# sensor_v5_no_gnd.net
KiCad netlist of a schematic drawn in EAGLE
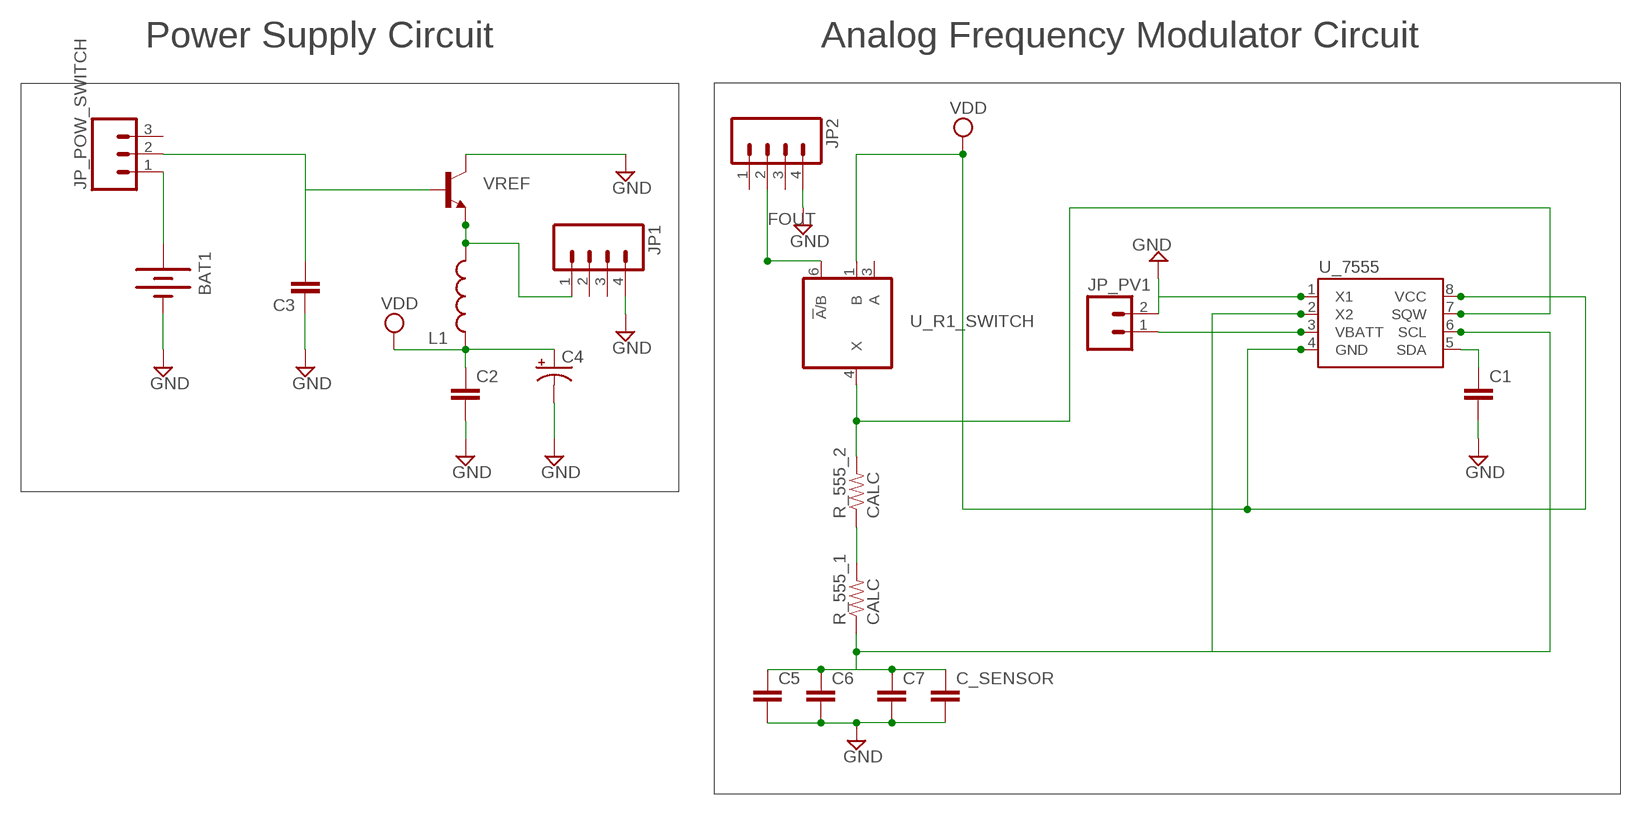
[diagram p0: schematic, sheet 1]

(export (version "E")
  (design (tool "Eeschema 10.0.6"))
  (components
    (comp (ref "BAT1")
      (value "BATTERY20PTH_LAB")
      (footprint "eagle-import:BATTCOM_20MM_PTH")
      (libsource (lib "eagle-import") (part "BATTERY20PTH_LAB"))
    )
    (comp (ref "C1")
      (value "CAP0603-CAP")
      (footprint "eagle-import:0603-CAP")
      (libsource (lib "eagle-import") (part "SparkFun-Capacitors_CAP0603-CAP"))
    )
    (comp (ref "C2")
      (value "CAP0603-CAP")
      (footprint "eagle-import:0603-CAP")
      (libsource (lib "eagle-import") (part "SparkFun-Capacitors_CAP0603-CAP"))
    )
    (comp (ref "C3")
      (value "CAP0603-CAP")
      (footprint "eagle-import:0603-CAP")
      (libsource (lib "eagle-import") (part "SparkFun-Capacitors_CAP0603-CAP"))
    )
    (comp (ref "C4")
      (value "CAP_POL1206")
      (footprint "eagle-import:EIA3216")
      (libsource (lib "eagle-import") (part "CAP_POL1206"))
    )
    (comp (ref "C5")
      (value "CAP0805")
      (footprint "eagle-import:0805")
      (libsource (lib "eagle-import") (part "CAP0805"))
    )
    (comp (ref "C6")
      (value "CAP0805")
      (footprint "eagle-import:0805")
      (libsource (lib "eagle-import") (part "CAP0805"))
    )
    (comp (ref "C7")
      (value "CAP0805")
      (footprint "eagle-import:0805")
      (libsource (lib "eagle-import") (part "CAP0805"))
    )
    (comp (ref "C_SENSOR")
      (value "CAP0805")
      (footprint "eagle-import:0805")
      (libsource (lib "eagle-import") (part "CAP0805"))
    )
    (comp (ref "JP1")
      (value "M04LOCK")
      (footprint "eagle-import:1X04_LOCK")
      (libsource (lib "eagle-import") (part "M04LOCK"))
    )
    (comp (ref "JP2")
      (value "M04LOCK")
      (footprint "eagle-import:1X04_LOCK")
      (libsource (lib "eagle-import") (part "M04LOCK"))
    )
    (comp (ref "JP_POW_SWITCH")
      (value "M03LOCK")
      (footprint "eagle-import:1X03_LOCK")
      (libsource (lib "eagle-import") (part "M03LOCK"))
    )
    (comp (ref "JP_PV1")
      (value "M02LOCK")
      (footprint "eagle-import:1X02_LOCK")
      (libsource (lib "eagle-import") (part "M02LOCK"))
    )
    (comp (ref "L1")
      (value "INDUCTOR0603")
      (footprint "eagle-import:0603")
      (libsource (lib "eagle-import") (part "INDUCTOR0603"))
    )
    (comp (ref "R_555_1")
      (value "CALC")
      (footprint "eagle-import:0805")
      (libsource (lib "eagle-import") (part "RESISTOR0805-RES"))
    )
    (comp (ref "R_555_2")
      (value "CALC")
      (footprint "eagle-import:0805")
      (libsource (lib "eagle-import") (part "RESISTOR0805-RES"))
    )
    (comp (ref "U_7555")
      (value "DS1307SO8")
      (footprint "eagle-import:SO08")
      (libsource (lib "eagle-import") (part "DS1307SO8"))
    )
    (comp (ref "U_R1_SWITCH")
      (value "741G3157DCKR")
      (footprint "eagle-import:DCK_R-PDSO-G6")
      (libsource (lib "eagle-import") (part "741G3157DCKR"))
    )
    (comp (ref "U_VREF")
      (value "TRANSISTOR_NPNSOT23-3")
      (footprint "eagle-import:SOT23-3")
      (libsource (lib "eagle-import") (part "TRANSISTOR_NPNSOT23-3"))
    )
  )
  (nets
    (net (code "1") (name "/FOUT") (class "Default")
      (node (ref "JP2") (pin "2") (pinfunction "2_2") (pintype "passive"))
      (node (ref "JP_PV1") (pin "1") (pinfunction "1_1") (pintype "passive"))
      (node (ref "U_7555") (pin "3") (pinfunction "VBATT_3") (pintype "bidirectional"))
      (node (ref "U_R1_SWITCH") (pin "6") (pinfunction "~{A}/B_6") (pintype "input"))
    )
    (net (code "2") (name "/P2") (class "Default")
      (node (ref "C5") (pin "1") (pinfunction "1_1") (pintype "passive"))
      (node (ref "C6") (pin "1") (pinfunction "1_1") (pintype "passive"))
      (node (ref "C7") (pin "1") (pinfunction "1_1") (pintype "passive"))
      (node (ref "C_SENSOR") (pin "1") (pinfunction "1_1") (pintype "passive"))
      (node (ref "R_555_1") (pin "1") (pinfunction "1_1") (pintype "passive"))
      (node (ref "U_7555") (pin "2") (pinfunction "X2_2") (pintype "bidirectional"))
      (node (ref "U_7555") (pin "6") (pinfunction "SCL_6") (pintype "bidirectional"))
    )
    (net (code "3") (name "GND") (class "Default")
      (node (ref "BAT1") (pin "2") (pinfunction "-_2") (pintype "power_in"))
      (node (ref "C1") (pin "2") (pinfunction "2_2") (pintype "passive"))
      (node (ref "C2") (pin "2") (pinfunction "2_2") (pintype "passive"))
      (node (ref "C3") (pin "1") (pinfunction "1_1") (pintype "passive"))
      (node (ref "C4") (pin "C") (pinfunction "-_C") (pintype "passive"))
      (node (ref "C5") (pin "2") (pinfunction "2_2") (pintype "passive"))
      (node (ref "C6") (pin "2") (pinfunction "2_2") (pintype "passive"))
      (node (ref "C7") (pin "2") (pinfunction "2_2") (pintype "passive"))
      (node (ref "C_SENSOR") (pin "2") (pinfunction "2_2") (pintype "passive"))
      (node (ref "JP1") (pin "4") (pinfunction "4_4") (pintype "passive"))
      (node (ref "JP2") (pin "4") (pinfunction "4_4") (pintype "passive"))
      (node (ref "JP_PV1") (pin "2") (pinfunction "2_2") (pintype "passive"))
      (node (ref "U_7555") (pin "1") (pinfunction "X1_1") (pintype "bidirectional"))
      (node (ref "U_VREF") (pin "3") (pinfunction "C_3") (pintype "passive"))
    )
    (net (code "4") (name "Net-(BAT1-+)") (class "Default")
      (node (ref "BAT1") (pin "1") (pinfunction "+_1") (pintype "power_in"))
      (node (ref "JP_POW_SWITCH") (pin "1") (pinfunction "1_1") (pintype "passive"))
    )
    (net (code "5") (name "Net-(R_555_1-Pad2)") (class "Default")
      (node (ref "R_555_1") (pin "2") (pinfunction "2_2") (pintype "passive"))
      (node (ref "R_555_2") (pin "1") (pinfunction "1_1") (pintype "passive"))
    )
    (net (code "6") (name "Net-(U_7555-SDA)") (class "Default")
      (node (ref "C1") (pin "1") (pinfunction "1_1") (pintype "passive"))
      (node (ref "U_7555") (pin "5") (pinfunction "SDA_5") (pintype "bidirectional"))
    )
    (net (code "7") (name "Net-(U_7555-SQW)") (class "Default")
      (node (ref "R_555_2") (pin "2") (pinfunction "2_2") (pintype "passive"))
      (node (ref "U_7555") (pin "7") (pinfunction "SQW_7") (pintype "bidirectional"))
      (node (ref "U_R1_SWITCH") (pin "4") (pinfunction "X_4") (pintype "bidirectional"))
    )
    (net (code "8") (name "Net-(U_VREF-B)") (class "Default")
      (node (ref "C3") (pin "2") (pinfunction "2_2") (pintype "passive"))
      (node (ref "JP_POW_SWITCH") (pin "2") (pinfunction "2_2") (pintype "passive"))
      (node (ref "U_VREF") (pin "1") (pinfunction "B_1") (pintype "passive"))
    )
    (net (code "9") (name "Net-(U_VREF-E)") (class "Default")
      (node (ref "JP1") (pin "1") (pinfunction "1_1") (pintype "passive"))
      (node (ref "L1") (pin "2") (pinfunction "2_2") (pintype "passive"))
      (node (ref "U_VREF") (pin "2") (pinfunction "E_2") (pintype "passive"))
    )
    (net (code "10") (name "VDD") (class "Default")
      (node (ref "C2") (pin "1") (pinfunction "1_1") (pintype "passive"))
      (node (ref "C4") (pin "A") (pinfunction "+_A") (pintype "passive"))
      (node (ref "L1") (pin "1") (pinfunction "1_1") (pintype "passive"))
      (node (ref "U_7555") (pin "4") (pinfunction "GND_4") (pintype "bidirectional"))
      (node (ref "U_7555") (pin "8") (pinfunction "VCC_8") (pintype "bidirectional"))
      (node (ref "U_R1_SWITCH") (pin "1") (pinfunction "B_1") (pintype "bidirectional"))
    )
    (net (code "11") (name "unconnected-(JP1-Pad2)") (class "Default")
      (node (ref "JP1") (pin "2") (pinfunction "2_2") (pintype "passive"))
    )
    (net (code "12") (name "unconnected-(JP1-Pad3)") (class "Default")
      (node (ref "JP1") (pin "3") (pinfunction "3_3") (pintype "passive"))
    )
    (net (code "13") (name "unconnected-(JP2-Pad1)") (class "Default")
      (node (ref "JP2") (pin "1") (pinfunction "1_1") (pintype "passive"))
    )
    (net (code "14") (name "unconnected-(JP2-Pad3)") (class "Default")
      (node (ref "JP2") (pin "3") (pinfunction "3_3") (pintype "passive"))
    )
    (net (code "15") (name "unconnected-(JP_POW_SWITCH-Pad3)") (class "Default")
      (node (ref "JP_POW_SWITCH") (pin "3") (pinfunction "3_3") (pintype "passive"))
    )
    (net (code "16") (name "unconnected-(U_R1_SWITCHA-A-Pad3)") (class "Default")
      (node (ref "U_R1_SWITCH") (pin "3") (pinfunction "A_3") (pintype "bidirectional"))
    )
  )
)
